# 2_4G.net
KiCad netlist of a schematic drawn in EasyEDA Pro
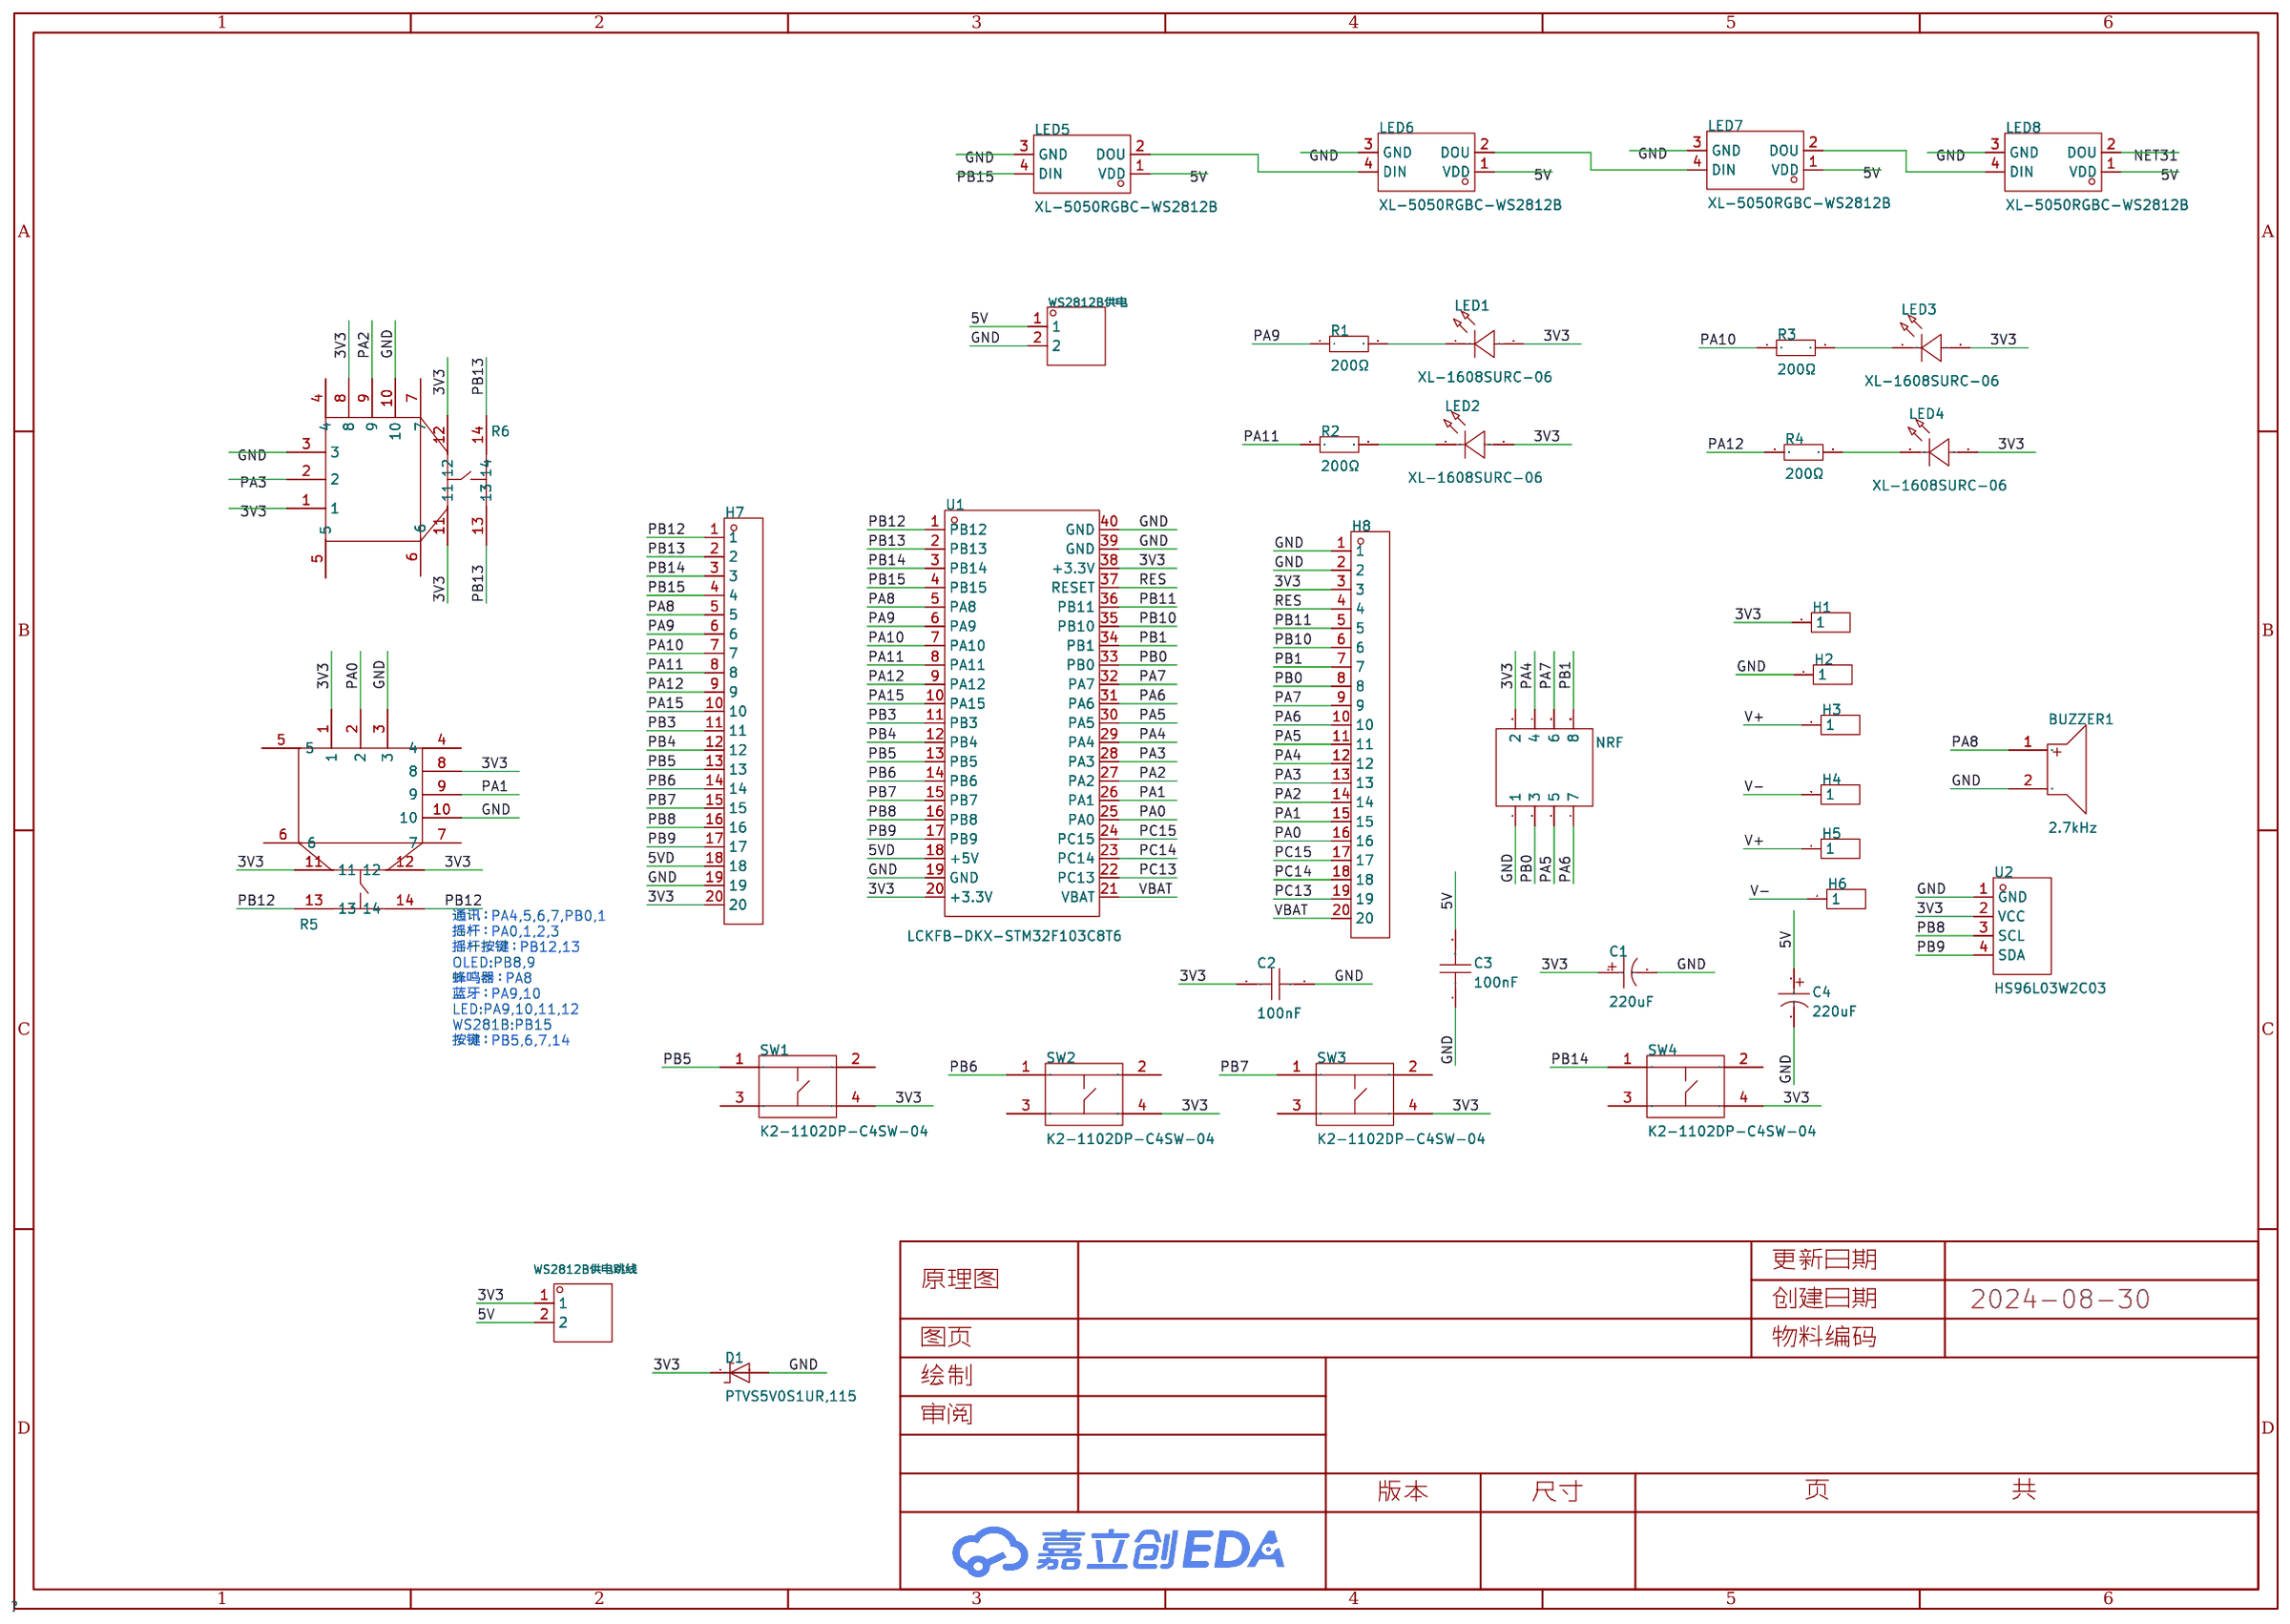
[diagram p0: schematic sheet]

(export (version "E")
  (design (tool "Eeschema 10.0.6"))
  (components
    (comp (ref "BUZZER1")
      (value "2.7kHz")
      (footprint "easyedapro:BUZ-TH_BD9.0-P4.00-D0.6-FD")
      (description "驱动方式:无源(外部驱动);构造类型:电磁式;频率:2.7kHz;声压(SPL):85dB@3V,10cm;")
      (fields (field (name "Manufacturer Part") "QMB-09B-03") (field (name "Manufacturer") "华能"))
      (libsource (lib "easyedapro") (part "QMB-09B-03"))
    )
    (comp (ref "C1")
      (value "220uF")
      (footprint "easyedapro:CAP-TH_BD8.0-P3.50-D0.6-FD")
      (description "容值:220uF;精度:±20%;额定电压:35V;")
      (fields (field (name "Manufacturer Part") "ERS1VM221F12OT") (field (name "Manufacturer") "AISHI(艾华集团)"))
      (libsource (lib "easyedapro") (part "ERS1VM221F12OT"))
    )
    (comp (ref "C2")
      (value "100nF")
      (footprint "easyedapro:C0603")
      (description "容值:100nF;精度:±10%;额定电压:50V;材质(温度系数):X7R;")
      (fields
        (field (name "Manufacturer Part") "CGA0603X7R104K500JT")
        (field (name "Manufacturer") "HRE(芯声)")
      )
      (libsource (lib "easyedapro") (part "CGA0603X7R104K500JT"))
    )
    (comp (ref "C3")
      (value "100nF")
      (footprint "easyedapro:C0603")
      (description "容值:100nF;精度:±10%;额定电压:50V;材质(温度系数):X7R;")
      (fields
        (field (name "Manufacturer Part") "CGA0603X7R104K500JT")
        (field (name "Manufacturer") "HRE(芯声)")
      )
      (libsource (lib "easyedapro") (part "CGA0603X7R104K500JT"))
    )
    (comp (ref "C4")
      (value "220uF")
      (footprint "easyedapro:CAP-TH_BD8.0-P3.50-D0.6-FD")
      (description "容值:220uF;精度:±20%;额定电压:35V;")
      (fields (field (name "Manufacturer Part") "ERS1VM221F12OT") (field (name "Manufacturer") "AISHI(艾华集团)"))
      (libsource (lib "easyedapro") (part "ERS1VM221F12OT"))
    )
    (comp (ref "D1")
      (value "PTVS5V0S1UR,115")
      (footprint "easyedapro:SOD-123_L2.8-W1.8-LS3.7-RD")
      (description "极性:单向;反向截止电压(Vrwm):5V;击穿电压(最小值):6.4V;峰值脉冲电流(Ipp)@10/1000μs:43.5A;最大钳位电压:9.2V;")
      (fields (field (name "Manufacturer") "Nexperia(安世)"))
      (libsource (lib "easyedapro") (part "PTVS5V0S1UR,115"))
    )
    (comp (ref "H1")
      (value "~")
      (footprint "easyedapro:HDR-TH_1P-V-M_XKB_X4611WV-01I-C28D40")
      (libsource (lib "easyedapro") (part "HDR_1x1"))
    )
    (comp (ref "H2")
      (value "~")
      (footprint "easyedapro:HDR-TH_1P-V-M_XKB_X4611WV-01I-C28D40")
      (libsource (lib "easyedapro") (part "HDR_1x1"))
    )
    (comp (ref "H3")
      (value "~")
      (footprint "easyedapro:HDR-TH_1P-V-M_XKB_X4611WV-01I-C28D40")
      (libsource (lib "easyedapro") (part "HDR_1x1"))
    )
    (comp (ref "H4")
      (value "~")
      (footprint "easyedapro:HDR-TH_1P-V-M_XKB_X4611WV-01I-C28D40")
      (libsource (lib "easyedapro") (part "HDR_1x1"))
    )
    (comp (ref "H5")
      (value "~")
      (footprint "easyedapro:HDR-TH_1P-V-M_XKB_X4611WV-01I-C28D40")
      (libsource (lib "easyedapro") (part "HDR_1x1"))
    )
    (comp (ref "H6")
      (value "~")
      (footprint "easyedapro:HDR-TH_1P-V-M_XKB_X4611WV-01I-C28D40")
      (libsource (lib "easyedapro") (part "HDR_1x1"))
    )
    (comp (ref "H7")
      (value "~")
      (footprint "easyedapro:HDR-TH_20P-P2.54-V-M-1")
      (libsource (lib "easyedapro") (part "HDR_2.54-1x20P"))
    )
    (comp (ref "H8")
      (value "~")
      (footprint "easyedapro:HDR-TH_20P-P2.54-V-M-1")
      (libsource (lib "easyedapro") (part "HDR_2.54-1x20P"))
    )
    (comp (ref "LED1")
      (value "XL-1608SURC-06")
      (footprint "easyedapro:LED0603-RD_RED")
      (description "发光颜色:红色;功率:55mW;正向电流:25mA;主波长:617nm~621nm;透镜颜色:无色透明透镜;色温:-;发光角度:120°;载带方式:正贴;工作温度:-30°C~+85°C;")
      (fields (field (name "Manufacturer") "XINGLIGHT(成兴光)"))
      (libsource (lib "easyedapro") (part "XL-1608SURC-06"))
    )
    (comp (ref "LED2")
      (value "XL-1608SURC-06")
      (footprint "easyedapro:LED0603-RD_RED")
      (description "发光颜色:红色;功率:55mW;正向电流:25mA;主波长:617nm~621nm;透镜颜色:无色透明透镜;色温:-;发光角度:120°;载带方式:正贴;工作温度:-30°C~+85°C;")
      (fields (field (name "Manufacturer") "XINGLIGHT(成兴光)"))
      (libsource (lib "easyedapro") (part "XL-1608SURC-06"))
    )
    (comp (ref "LED3")
      (value "XL-1608SURC-06")
      (footprint "easyedapro:LED0603-RD_RED")
      (description "发光颜色:红色;功率:55mW;正向电流:25mA;主波长:617nm~621nm;透镜颜色:无色透明透镜;色温:-;发光角度:120°;载带方式:正贴;工作温度:-30°C~+85°C;")
      (fields (field (name "Manufacturer") "XINGLIGHT(成兴光)"))
      (libsource (lib "easyedapro") (part "XL-1608SURC-06"))
    )
    (comp (ref "LED4")
      (value "XL-1608SURC-06")
      (footprint "easyedapro:LED0603-RD_RED")
      (description "发光颜色:红色;功率:55mW;正向电流:25mA;主波长:617nm~621nm;透镜颜色:无色透明透镜;色温:-;发光角度:120°;载带方式:正贴;工作温度:-30°C~+85°C;")
      (fields (field (name "Manufacturer") "XINGLIGHT(成兴光)"))
      (libsource (lib "easyedapro") (part "XL-1608SURC-06"))
    )
    (comp (ref "LED5")
      (value "XL-5050RGBC-WS2812B")
      (footprint "easyedapro:LED-SMD_4P-L5.0-W5.0-BL_XL-5050RGBC")
      (description "5050七彩幻彩透明贴片LED灯珠 5050 幻彩透明四脚 ws2812B 内置驱动IC")
      (fields (field (name "Manufacturer") "XINGLIGHT(成兴光)"))
      (libsource (lib "easyedapro") (part "XL-5050RGBC-WS2812B"))
    )
    (comp (ref "LED6")
      (value "XL-5050RGBC-WS2812B")
      (footprint "easyedapro:LED-SMD_4P-L5.0-W5.0-BL_XL-5050RGBC")
      (description "5050七彩幻彩透明贴片LED灯珠 5050 幻彩透明四脚 ws2812B 内置驱动IC")
      (fields (field (name "Manufacturer") "XINGLIGHT(成兴光)"))
      (libsource (lib "easyedapro") (part "XL-5050RGBC-WS2812B"))
    )
    (comp (ref "LED7")
      (value "XL-5050RGBC-WS2812B")
      (footprint "easyedapro:LED-SMD_4P-L5.0-W5.0-BL_XL-5050RGBC")
      (description "5050七彩幻彩透明贴片LED灯珠 5050 幻彩透明四脚 ws2812B 内置驱动IC")
      (fields (field (name "Manufacturer") "XINGLIGHT(成兴光)"))
      (libsource (lib "easyedapro") (part "XL-5050RGBC-WS2812B"))
    )
    (comp (ref "LED8")
      (value "XL-5050RGBC-WS2812B")
      (footprint "easyedapro:LED-SMD_4P-L5.0-W5.0-BL_XL-5050RGBC")
      (description "5050七彩幻彩透明贴片LED灯珠 5050 幻彩透明四脚 ws2812B 内置驱动IC")
      (fields (field (name "Manufacturer") "XINGLIGHT(成兴光)"))
      (libsource (lib "easyedapro") (part "XL-5050RGBC-WS2812B"))
    )
    (comp (ref "NRF")
      (value "~")
      (footprint "easyedapro:HDR-TH_8P-P2.54-V-F-R2-C4-S2.54-1")
      (libsource (lib "easyedapro") (part "HDR-F-2.54_2x4"))
    )
    (comp (ref "R1")
      (value "200Ω")
      (footprint "easyedapro:R0603")
      (description "电阻类型:厚膜电阻;阻值:10kΩ;精度:±1%;功率:100mW;最大工作电压:75V;温度系数:±100ppm/°C;")
      (fields
        (field (name "Manufacturer Part") "0603WAF1002T5E")
        (field (name "Manufacturer") "UNI-ROYAL(厚声)")
      )
      (libsource (lib "easyedapro") (part "0603WAF1002T5E"))
    )
    (comp (ref "R2")
      (value "200Ω")
      (footprint "easyedapro:R0603")
      (description "电阻类型:厚膜电阻;阻值:10kΩ;精度:±1%;功率:100mW;最大工作电压:75V;温度系数:±100ppm/°C;")
      (fields
        (field (name "Manufacturer Part") "0603WAF1002T5E")
        (field (name "Manufacturer") "UNI-ROYAL(厚声)")
      )
      (libsource (lib "easyedapro") (part "0603WAF1002T5E"))
    )
    (comp (ref "R3")
      (value "200Ω")
      (footprint "easyedapro:R0603")
      (description "电阻类型:厚膜电阻;阻值:10kΩ;精度:±1%;功率:100mW;最大工作电压:75V;温度系数:±100ppm/°C;")
      (fields
        (field (name "Manufacturer Part") "0603WAF1002T5E")
        (field (name "Manufacturer") "UNI-ROYAL(厚声)")
      )
      (libsource (lib "easyedapro") (part "0603WAF1002T5E"))
    )
    (comp (ref "R4")
      (value "200Ω")
      (footprint "easyedapro:R0603")
      (description "电阻类型:厚膜电阻;阻值:10kΩ;精度:±1%;功率:100mW;最大工作电压:75V;温度系数:±100ppm/°C;")
      (fields
        (field (name "Manufacturer Part") "0603WAF1002T5E")
        (field (name "Manufacturer") "UNI-ROYAL(厚声)")
      )
      (libsource (lib "easyedapro") (part "0603WAF1002T5E"))
    )
    (comp (ref "R5") (value "~") (footprint "easyedapro:摇杆") (libsource (lib "easyedapro") (part "摇杆")))
    (comp (ref "R6") (value "~") (footprint "easyedapro:摇杆") (libsource (lib "easyedapro") (part "摇杆")))
    (comp (ref "SW1")
      (value "K2-1102DP-C4SW-04")
      (footprint "easyedapro:KEY-TH_4P-L6.0-W6.0-P4.50-LS6.50")
      (fields (field (name "Manufacturer") "韩国韩荣"))
      (libsource (lib "easyedapro") (part "K2-1102DP-C4SW-04"))
    )
    (comp (ref "SW2")
      (value "K2-1102DP-C4SW-04")
      (footprint "easyedapro:KEY-TH_4P-L6.0-W6.0-P4.50-LS6.50")
      (fields (field (name "Manufacturer") "韩国韩荣"))
      (libsource (lib "easyedapro") (part "K2-1102DP-C4SW-04"))
    )
    (comp (ref "SW3")
      (value "K2-1102DP-C4SW-04")
      (footprint "easyedapro:KEY-TH_4P-L6.0-W6.0-P4.50-LS6.50")
      (fields (field (name "Manufacturer") "韩国韩荣"))
      (libsource (lib "easyedapro") (part "K2-1102DP-C4SW-04"))
    )
    (comp (ref "SW4")
      (value "K2-1102DP-C4SW-04")
      (footprint "easyedapro:KEY-TH_4P-L6.0-W6.0-P4.50-LS6.50")
      (fields (field (name "Manufacturer") "韩国韩荣"))
      (libsource (lib "easyedapro") (part "K2-1102DP-C4SW-04"))
    )
    (comp (ref "U1")
      (value "LCKFB-DKX-STM32F103C8T6")
      (footprint "easyedapro:CONN-TH_L53.3-W22.9_STM32F103C8T6-CARD")
      (fields (field (name "Manufacturer") "立创开发板"))
      (libsource (lib "easyedapro") (part "LCKFB-DKX-STM32F103C8T6"))
    )
    (comp (ref "U2")
      (value "HS96L03W2C03")
      (footprint "easyedapro:OLED-TH_L27.8-W27.2-P2.54_C9900033791")
      (description "主控芯片:SSD1315;接口类型:I2C;尺寸(inch):0.96;像素分辨率:128x64;")
      (fields (field (name "Manufacturer") "HS(汉昇)"))
      (libsource (lib "easyedapro") (part "HS96L03W2C03"))
    )
    (comp (ref "WS2812B供电")
      (value "~")
      (footprint "easyedapro:HDR-TH_2P-P2.54-V-M-1")
      (libsource (lib "easyedapro") (part "210S-1*2P L=11.6MMGold-plated black"))
    )
    (comp (ref "WS2812B供电跳线")
      (value "~")
      (footprint "easyedapro:HDR-TH_2P-P2.54-V-M-1")
      (libsource (lib "easyedapro") (part "210S-1*2P L=11.6MMGold-plated black"))
    )
  )
  (nets
    (net (code "1") (name "/3V3") (class "Default")
      (node (ref "C1") (pin "1") (pinfunction "1_1") (pintype "input"))
      (node (ref "C2") (pin "1") (pinfunction "1_1") (pintype "unspecified"))
      (node (ref "D1") (pin "1") (pinfunction "C_1") (pintype "input"))
      (node (ref "H1") (pin "1") (pinfunction "1_1") (pintype "unspecified"))
      (node (ref "H7") (pin "20") (pinfunction "20_20") (pintype "input"))
      (node (ref "H8") (pin "3") (pinfunction "3_3") (pintype "input"))
      (node (ref "LED1") (pin "2") (pinfunction "A_2") (pintype "unspecified"))
      (node (ref "LED2") (pin "2") (pinfunction "A_2") (pintype "unspecified"))
      (node (ref "LED3") (pin "2") (pinfunction "A_2") (pintype "unspecified"))
      (node (ref "LED4") (pin "2") (pinfunction "A_2") (pintype "unspecified"))
      (node (ref "NRF") (pin "2") (pinfunction "2_2") (pintype "input"))
      (node (ref "R5") (pin "1") (pinfunction "1_1") (pintype "input"))
      (node (ref "R5") (pin "11") (pinfunction "11_11") (pintype "input"))
      (node (ref "R5") (pin "12") (pinfunction "12_12") (pintype "input"))
      (node (ref "R5") (pin "8") (pinfunction "8_8") (pintype "input"))
      (node (ref "R6") (pin "1") (pinfunction "1_1") (pintype "input"))
      (node (ref "R6") (pin "11") (pinfunction "11_11") (pintype "input"))
      (node (ref "R6") (pin "12") (pinfunction "12_12") (pintype "input"))
      (node (ref "R6") (pin "8") (pinfunction "8_8") (pintype "input"))
      (node (ref "SW1") (pin "4") (pinfunction "4_4") (pintype "unspecified"))
      (node (ref "SW2") (pin "4") (pinfunction "4_4") (pintype "unspecified"))
      (node (ref "SW3") (pin "4") (pinfunction "4_4") (pintype "unspecified"))
      (node (ref "SW4") (pin "4") (pinfunction "4_4") (pintype "unspecified"))
      (node (ref "U1") (pin "20") (pinfunction "+3.3V_20") (pintype "unspecified"))
      (node (ref "U1") (pin "38") (pinfunction "+3.3V_38") (pintype "unspecified"))
      (node (ref "U2") (pin "2") (pinfunction "VCC_2") (pintype "unspecified"))
      (node (ref "WS2812B供电跳线") (pin "1") (pinfunction "1_1") (pintype "input"))
    )
    (net (code "2") (name "/5V") (class "Default")
      (node (ref "C3") (pin "2") (pinfunction "2_2") (pintype "unspecified"))
      (node (ref "C4") (pin "1") (pinfunction "1_1") (pintype "input"))
      (node (ref "LED5") (pin "1") (pinfunction "VDD_1") (pintype "unspecified"))
      (node (ref "LED6") (pin "1") (pinfunction "VDD_1") (pintype "unspecified"))
      (node (ref "LED7") (pin "1") (pinfunction "VDD_1") (pintype "unspecified"))
      (node (ref "LED8") (pin "1") (pinfunction "VDD_1") (pintype "unspecified"))
      (node (ref "WS2812B供电") (pin "1") (pinfunction "1_1") (pintype "input"))
      (node (ref "WS2812B供电跳线") (pin "2") (pinfunction "2_2") (pintype "input"))
    )
    (net (code "3") (name "/5VD") (class "Default")
      (node (ref "H7") (pin "18") (pinfunction "18_18") (pintype "input"))
      (node (ref "U1") (pin "18") (pinfunction "+5V_18") (pintype "unspecified"))
    )
    (net (code "4") (name "/GND") (class "Default")
      (node (ref "BUZZER1") (pin "2") (pinfunction "2_2") (pintype "unspecified"))
      (node (ref "C1") (pin "2") (pinfunction "2_2") (pintype "input"))
      (node (ref "C2") (pin "2") (pinfunction "2_2") (pintype "unspecified"))
      (node (ref "C3") (pin "1") (pinfunction "1_1") (pintype "unspecified"))
      (node (ref "C4") (pin "2") (pinfunction "2_2") (pintype "input"))
      (node (ref "D1") (pin "2") (pinfunction "A_2") (pintype "input"))
      (node (ref "H2") (pin "1") (pinfunction "1_1") (pintype "unspecified"))
      (node (ref "H7") (pin "19") (pinfunction "19_19") (pintype "input"))
      (node (ref "H8") (pin "1") (pinfunction "1_1") (pintype "input"))
      (node (ref "H8") (pin "2") (pinfunction "2_2") (pintype "input"))
      (node (ref "LED5") (pin "3") (pinfunction "GND_3") (pintype "unspecified"))
      (node (ref "LED6") (pin "3") (pinfunction "GND_3") (pintype "unspecified"))
      (node (ref "LED7") (pin "3") (pinfunction "GND_3") (pintype "unspecified"))
      (node (ref "LED8") (pin "3") (pinfunction "GND_3") (pintype "unspecified"))
      (node (ref "NRF") (pin "1") (pinfunction "1_1") (pintype "input"))
      (node (ref "R5") (pin "10") (pinfunction "10_10") (pintype "input"))
      (node (ref "R5") (pin "3") (pinfunction "3_3") (pintype "input"))
      (node (ref "R6") (pin "10") (pinfunction "10_10") (pintype "input"))
      (node (ref "R6") (pin "3") (pinfunction "3_3") (pintype "input"))
      (node (ref "U1") (pin "19") (pinfunction "GND_19") (pintype "unspecified"))
      (node (ref "U1") (pin "39") (pinfunction "GND_39") (pintype "unspecified"))
      (node (ref "U1") (pin "40") (pinfunction "GND_40") (pintype "unspecified"))
      (node (ref "U2") (pin "1") (pinfunction "GND_1") (pintype "unspecified"))
      (node (ref "WS2812B供电") (pin "2") (pinfunction "2_2") (pintype "input"))
    )
    (net (code "5") (name "/NET31") (class "Default")
      (node (ref "LED8") (pin "2") (pinfunction "DOU_2") (pintype "unspecified"))
    )
    (net (code "6") (name "/PA0") (class "Default")
      (node (ref "H8") (pin "16") (pinfunction "16_16") (pintype "input"))
      (node (ref "R5") (pin "2") (pinfunction "2_2") (pintype "input"))
      (node (ref "U1") (pin "25") (pinfunction "PA0_25") (pintype "unspecified"))
    )
    (net (code "7") (name "/PA1") (class "Default")
      (node (ref "H8") (pin "15") (pinfunction "15_15") (pintype "input"))
      (node (ref "R5") (pin "9") (pinfunction "9_9") (pintype "input"))
      (node (ref "U1") (pin "26") (pinfunction "PA1_26") (pintype "unspecified"))
    )
    (net (code "8") (name "/PA2") (class "Default")
      (node (ref "H8") (pin "14") (pinfunction "14_14") (pintype "input"))
      (node (ref "R6") (pin "9") (pinfunction "9_9") (pintype "input"))
      (node (ref "U1") (pin "27") (pinfunction "PA2_27") (pintype "unspecified"))
    )
    (net (code "9") (name "/PA3") (class "Default")
      (node (ref "H8") (pin "13") (pinfunction "13_13") (pintype "input"))
      (node (ref "R6") (pin "2") (pinfunction "2_2") (pintype "input"))
      (node (ref "U1") (pin "28") (pinfunction "PA3_28") (pintype "unspecified"))
    )
    (net (code "10") (name "/PA4") (class "Default")
      (node (ref "H8") (pin "12") (pinfunction "12_12") (pintype "input"))
      (node (ref "NRF") (pin "4") (pinfunction "4_4") (pintype "input"))
      (node (ref "U1") (pin "29") (pinfunction "PA4_29") (pintype "unspecified"))
    )
    (net (code "11") (name "/PA5") (class "Default")
      (node (ref "H8") (pin "11") (pinfunction "11_11") (pintype "input"))
      (node (ref "NRF") (pin "5") (pinfunction "5_5") (pintype "input"))
      (node (ref "U1") (pin "30") (pinfunction "PA5_30") (pintype "unspecified"))
    )
    (net (code "12") (name "/PA6") (class "Default")
      (node (ref "H8") (pin "10") (pinfunction "10_10") (pintype "input"))
      (node (ref "NRF") (pin "7") (pinfunction "7_7") (pintype "input"))
      (node (ref "U1") (pin "31") (pinfunction "PA6_31") (pintype "unspecified"))
    )
    (net (code "13") (name "/PA7") (class "Default")
      (node (ref "H8") (pin "9") (pinfunction "9_9") (pintype "input"))
      (node (ref "NRF") (pin "6") (pinfunction "6_6") (pintype "input"))
      (node (ref "U1") (pin "32") (pinfunction "PA7_32") (pintype "unspecified"))
    )
    (net (code "14") (name "/PA8") (class "Default")
      (node (ref "BUZZER1") (pin "1") (pinfunction "1_1") (pintype "unspecified"))
      (node (ref "H7") (pin "5") (pinfunction "5_5") (pintype "input"))
      (node (ref "U1") (pin "5") (pinfunction "PA8_5") (pintype "unspecified"))
    )
    (net (code "15") (name "/PA9") (class "Default")
      (node (ref "H7") (pin "6") (pinfunction "6_6") (pintype "input"))
      (node (ref "R1") (pin "1") (pinfunction "1_1") (pintype "input"))
      (node (ref "U1") (pin "6") (pinfunction "PA9_6") (pintype "unspecified"))
    )
    (net (code "16") (name "/PA10") (class "Default")
      (node (ref "H7") (pin "7") (pinfunction "7_7") (pintype "input"))
      (node (ref "R3") (pin "1") (pinfunction "1_1") (pintype "input"))
      (node (ref "U1") (pin "7") (pinfunction "PA10_7") (pintype "unspecified"))
    )
    (net (code "17") (name "/PA11") (class "Default")
      (node (ref "H7") (pin "8") (pinfunction "8_8") (pintype "input"))
      (node (ref "R2") (pin "1") (pinfunction "1_1") (pintype "input"))
      (node (ref "U1") (pin "8") (pinfunction "PA11_8") (pintype "unspecified"))
    )
    (net (code "18") (name "/PA12") (class "Default")
      (node (ref "H7") (pin "9") (pinfunction "9_9") (pintype "input"))
      (node (ref "R4") (pin "1") (pinfunction "1_1") (pintype "input"))
      (node (ref "U1") (pin "9") (pinfunction "PA12_9") (pintype "unspecified"))
    )
    (net (code "19") (name "/PA15") (class "Default")
      (node (ref "H7") (pin "10") (pinfunction "10_10") (pintype "input"))
      (node (ref "U1") (pin "10") (pinfunction "PA15_10") (pintype "unspecified"))
    )
    (net (code "20") (name "/PB0") (class "Default")
      (node (ref "H8") (pin "8") (pinfunction "8_8") (pintype "input"))
      (node (ref "NRF") (pin "3") (pinfunction "3_3") (pintype "input"))
      (node (ref "U1") (pin "33") (pinfunction "PB0_33") (pintype "unspecified"))
    )
    (net (code "21") (name "/PB1") (class "Default")
      (node (ref "H8") (pin "7") (pinfunction "7_7") (pintype "input"))
      (node (ref "NRF") (pin "8") (pinfunction "8_8") (pintype "input"))
      (node (ref "U1") (pin "34") (pinfunction "PB1_34") (pintype "unspecified"))
    )
    (net (code "22") (name "/PB3") (class "Default")
      (node (ref "H7") (pin "11") (pinfunction "11_11") (pintype "input"))
      (node (ref "U1") (pin "11") (pinfunction "PB3_11") (pintype "unspecified"))
    )
    (net (code "23") (name "/PB4") (class "Default")
      (node (ref "H7") (pin "12") (pinfunction "12_12") (pintype "input"))
      (node (ref "U1") (pin "12") (pinfunction "PB4_12") (pintype "unspecified"))
    )
    (net (code "24") (name "/PB5") (class "Default")
      (node (ref "H7") (pin "13") (pinfunction "13_13") (pintype "input"))
      (node (ref "SW1") (pin "1") (pinfunction "1_1") (pintype "unspecified"))
      (node (ref "U1") (pin "13") (pinfunction "PB5_13") (pintype "unspecified"))
    )
    (net (code "25") (name "/PB6") (class "Default")
      (node (ref "H7") (pin "14") (pinfunction "14_14") (pintype "input"))
      (node (ref "SW2") (pin "1") (pinfunction "1_1") (pintype "unspecified"))
      (node (ref "U1") (pin "14") (pinfunction "PB6_14") (pintype "unspecified"))
    )
    (net (code "26") (name "/PB7") (class "Default")
      (node (ref "H7") (pin "15") (pinfunction "15_15") (pintype "input"))
      (node (ref "SW3") (pin "1") (pinfunction "1_1") (pintype "unspecified"))
      (node (ref "U1") (pin "15") (pinfunction "PB7_15") (pintype "unspecified"))
    )
    (net (code "27") (name "/PB8") (class "Default")
      (node (ref "H7") (pin "16") (pinfunction "16_16") (pintype "input"))
      (node (ref "U1") (pin "16") (pinfunction "PB8_16") (pintype "unspecified"))
      (node (ref "U2") (pin "3") (pinfunction "SCL_3") (pintype "unspecified"))
    )
    (net (code "28") (name "/PB9") (class "Default")
      (node (ref "H7") (pin "17") (pinfunction "17_17") (pintype "input"))
      (node (ref "U1") (pin "17") (pinfunction "PB9_17") (pintype "unspecified"))
      (node (ref "U2") (pin "4") (pinfunction "SDA_4") (pintype "unspecified"))
    )
    (net (code "29") (name "/PB10") (class "Default")
      (node (ref "H8") (pin "6") (pinfunction "6_6") (pintype "input"))
      (node (ref "U1") (pin "35") (pinfunction "PB10_35") (pintype "unspecified"))
    )
    (net (code "30") (name "/PB11") (class "Default")
      (node (ref "H8") (pin "5") (pinfunction "5_5") (pintype "input"))
      (node (ref "U1") (pin "36") (pinfunction "PB11_36") (pintype "unspecified"))
    )
    (net (code "31") (name "/PB12") (class "Default")
      (node (ref "H7") (pin "1") (pinfunction "1_1") (pintype "input"))
      (node (ref "R5") (pin "13") (pinfunction "13_13") (pintype "input"))
      (node (ref "R5") (pin "14") (pinfunction "14_14") (pintype "input"))
      (node (ref "U1") (pin "1") (pinfunction "PB12_1") (pintype "unspecified"))
    )
    (net (code "32") (name "/PB13") (class "Default")
      (node (ref "H7") (pin "2") (pinfunction "2_2") (pintype "input"))
      (node (ref "R6") (pin "13") (pinfunction "13_13") (pintype "input"))
      (node (ref "R6") (pin "14") (pinfunction "14_14") (pintype "input"))
      (node (ref "U1") (pin "2") (pinfunction "PB13_2") (pintype "unspecified"))
    )
    (net (code "33") (name "/PB14") (class "Default")
      (node (ref "H7") (pin "3") (pinfunction "3_3") (pintype "input"))
      (node (ref "SW4") (pin "1") (pinfunction "1_1") (pintype "unspecified"))
      (node (ref "U1") (pin "3") (pinfunction "PB14_3") (pintype "unspecified"))
    )
    (net (code "34") (name "/PB15") (class "Default")
      (node (ref "H7") (pin "4") (pinfunction "4_4") (pintype "input"))
      (node (ref "LED5") (pin "4") (pinfunction "DIN_4") (pintype "unspecified"))
      (node (ref "U1") (pin "4") (pinfunction "PB15_4") (pintype "unspecified"))
    )
    (net (code "35") (name "/PC13") (class "Default")
      (node (ref "H8") (pin "19") (pinfunction "19_19") (pintype "input"))
      (node (ref "U1") (pin "22") (pinfunction "PC13_22") (pintype "unspecified"))
    )
    (net (code "36") (name "/PC14") (class "Default")
      (node (ref "H8") (pin "18") (pinfunction "18_18") (pintype "input"))
      (node (ref "U1") (pin "23") (pinfunction "PC14_23") (pintype "unspecified"))
    )
    (net (code "37") (name "/PC15") (class "Default")
      (node (ref "H8") (pin "17") (pinfunction "17_17") (pintype "input"))
      (node (ref "U1") (pin "24") (pinfunction "PC15_24") (pintype "unspecified"))
    )
    (net (code "38") (name "/RES") (class "Default")
      (node (ref "H8") (pin "4") (pinfunction "4_4") (pintype "input"))
      (node (ref "U1") (pin "37") (pinfunction "RESET_37") (pintype "unspecified"))
    )
    (net (code "39") (name "/V+") (class "Default")
      (node (ref "H3") (pin "1") (pinfunction "1_1") (pintype "unspecified"))
      (node (ref "H5") (pin "1") (pinfunction "1_1") (pintype "unspecified"))
    )
    (net (code "40") (name "/V-") (class "Default")
      (node (ref "H4") (pin "1") (pinfunction "1_1") (pintype "unspecified"))
      (node (ref "H6") (pin "1") (pinfunction "1_1") (pintype "unspecified"))
    )
    (net (code "41") (name "/VBAT") (class "Default")
      (node (ref "H8") (pin "20") (pinfunction "20_20") (pintype "input"))
      (node (ref "U1") (pin "21") (pinfunction "VBAT_21") (pintype "unspecified"))
    )
    (net (code "42") (name "Net-(LED1-K)") (class "Default")
      (node (ref "LED1") (pin "1") (pinfunction "K_1") (pintype "unspecified"))
      (node (ref "R1") (pin "2") (pinfunction "2_2") (pintype "input"))
    )
    (net (code "43") (name "Net-(LED2-K)") (class "Default")
      (node (ref "LED2") (pin "1") (pinfunction "K_1") (pintype "unspecified"))
      (node (ref "R2") (pin "2") (pinfunction "2_2") (pintype "input"))
    )
    (net (code "44") (name "Net-(LED3-K)") (class "Default")
      (node (ref "LED3") (pin "1") (pinfunction "K_1") (pintype "unspecified"))
      (node (ref "R3") (pin "2") (pinfunction "2_2") (pintype "input"))
    )
    (net (code "45") (name "Net-(LED4-K)") (class "Default")
      (node (ref "LED4") (pin "1") (pinfunction "K_1") (pintype "unspecified"))
      (node (ref "R4") (pin "2") (pinfunction "2_2") (pintype "input"))
    )
    (net (code "46") (name "Net-(LED5-DOU)") (class "Default")
      (node (ref "LED5") (pin "2") (pinfunction "DOU_2") (pintype "unspecified"))
      (node (ref "LED6") (pin "4") (pinfunction "DIN_4") (pintype "unspecified"))
    )
    (net (code "47") (name "Net-(LED6-DOU)") (class "Default")
      (node (ref "LED6") (pin "2") (pinfunction "DOU_2") (pintype "unspecified"))
      (node (ref "LED7") (pin "4") (pinfunction "DIN_4") (pintype "unspecified"))
    )
    (net (code "48") (name "Net-(LED7-DOU)") (class "Default")
      (node (ref "LED7") (pin "2") (pinfunction "DOU_2") (pintype "unspecified"))
      (node (ref "LED8") (pin "4") (pinfunction "DIN_4") (pintype "unspecified"))
    )
    (net (code "49") (name "unconnected-(R5-Pad4)") (class "Default")
      (node (ref "R5") (pin "4") (pinfunction "4_4") (pintype "input"))
    )
    (net (code "50") (name "unconnected-(R5-Pad5)") (class "Default")
      (node (ref "R5") (pin "5") (pinfunction "5_5") (pintype "input"))
    )
    (net (code "51") (name "unconnected-(R5-Pad6)") (class "Default")
      (node (ref "R5") (pin "6") (pinfunction "6_6") (pintype "input"))
    )
    (net (code "52") (name "unconnected-(R5-Pad7)") (class "Default")
      (node (ref "R5") (pin "7") (pinfunction "7_7") (pintype "input"))
    )
    (net (code "53") (name "unconnected-(R6-Pad4)") (class "Default")
      (node (ref "R6") (pin "4") (pinfunction "4_4") (pintype "input"))
    )
    (net (code "54") (name "unconnected-(R6-Pad5)") (class "Default")
      (node (ref "R6") (pin "5") (pinfunction "5_5") (pintype "input"))
    )
    (net (code "55") (name "unconnected-(R6-Pad6)") (class "Default")
      (node (ref "R6") (pin "6") (pinfunction "6_6") (pintype "input"))
    )
    (net (code "56") (name "unconnected-(R6-Pad7)") (class "Default")
      (node (ref "R6") (pin "7") (pinfunction "7_7") (pintype "input"))
    )
    (net (code "57") (name "unconnected-(SW1-Pad2)") (class "Default")
      (node (ref "SW1") (pin "2") (pinfunction "2_2") (pintype "unspecified"))
    )
    (net (code "58") (name "unconnected-(SW1-Pad3)") (class "Default")
      (node (ref "SW1") (pin "3") (pinfunction "3_3") (pintype "unspecified"))
    )
    (net (code "59") (name "unconnected-(SW2-Pad2)") (class "Default")
      (node (ref "SW2") (pin "2") (pinfunction "2_2") (pintype "unspecified"))
    )
    (net (code "60") (name "unconnected-(SW2-Pad3)") (class "Default")
      (node (ref "SW2") (pin "3") (pinfunction "3_3") (pintype "unspecified"))
    )
    (net (code "61") (name "unconnected-(SW3-Pad2)") (class "Default")
      (node (ref "SW3") (pin "2") (pinfunction "2_2") (pintype "unspecified"))
    )
    (net (code "62") (name "unconnected-(SW3-Pad3)") (class "Default")
      (node (ref "SW3") (pin "3") (pinfunction "3_3") (pintype "unspecified"))
    )
    (net (code "63") (name "unconnected-(SW4-Pad2)") (class "Default")
      (node (ref "SW4") (pin "2") (pinfunction "2_2") (pintype "unspecified"))
    )
    (net (code "64") (name "unconnected-(SW4-Pad3)") (class "Default")
      (node (ref "SW4") (pin "3") (pinfunction "3_3") (pintype "unspecified"))
    )
  )
)
